# Guide_laser.net
KiCad netlist of a schematic drawn in Altium Designer
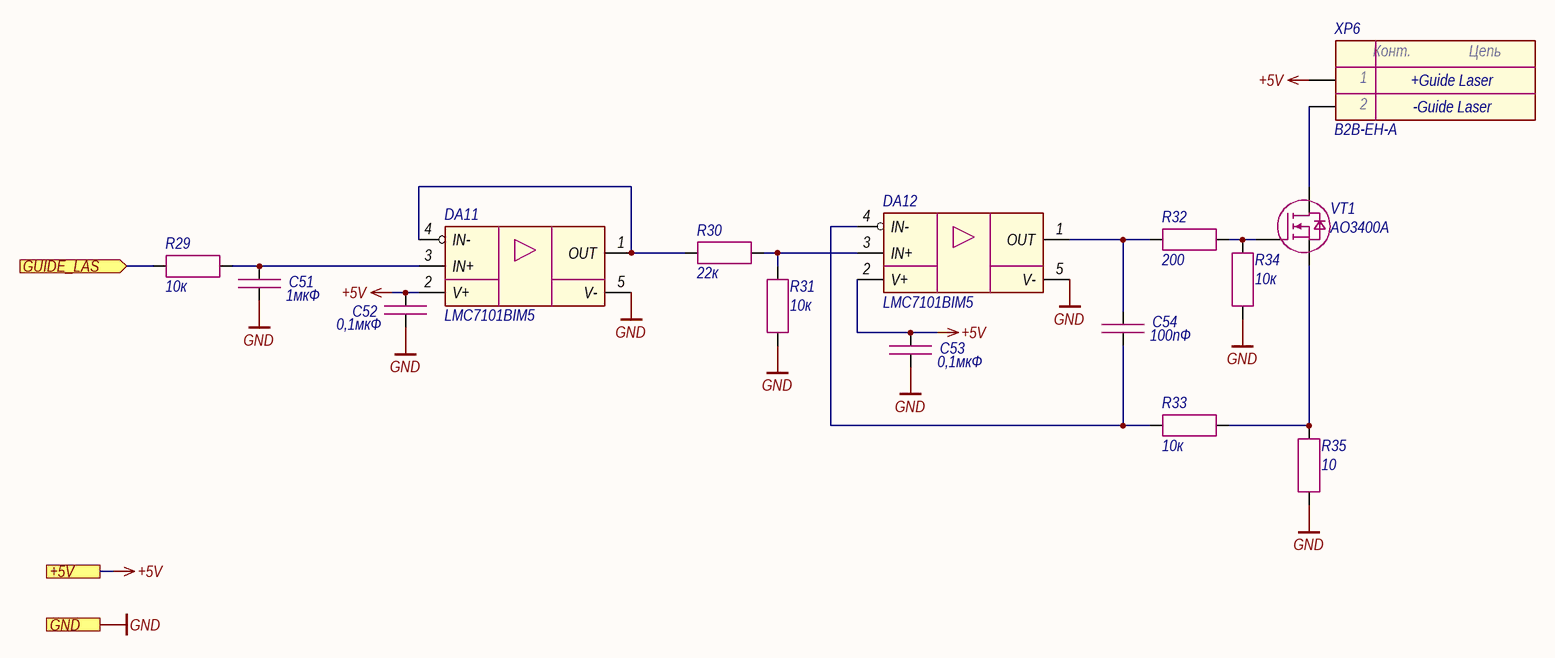
[diagram p0: Guide_laser.SchDoc]

(export (version "E")
  (design (tool "Eeschema 10.0.6"))
  (components
    (comp (ref "C51")
      (value "1мкФ")
      (footprint "Pcb_library:CAP_0603")
      (fields (field (name "MANUFACTURER") "Murata"))
      (libsource (lib "Schem_library") (part "Capacitor"))
    )
    (comp (ref "C52")
      (value "0,1мкФ")
      (footprint "Pcb_library:CAP_0603")
      (fields (field (name "MANUFACTURER") "Murata"))
      (libsource (lib "Schem_library") (part "Capacitor"))
    )
    (comp (ref "C53")
      (value "0,1мкФ")
      (footprint "Pcb_library:CAP_0603")
      (fields (field (name "MANUFACTURER") "Murata"))
      (libsource (lib "Schem_library") (part "Capacitor"))
    )
    (comp (ref "C54")
      (value "100пФ")
      (footprint "Pcb_library:CAP_0603")
      (fields (field (name "MANUFACTURER") "Murata"))
      (libsource (lib "Schem_library") (part "Capacitor"))
    )
    (comp (ref "DA11")
      (value "LMC7101BIM5")
      (footprint "Pcb_library:SOT-23-5")
      (fields (field (name "MANUFACTURER") "Texas Instruments"))
      (libsource (lib "Schem_library") (part "LMC7101"))
    )
    (comp (ref "DA12")
      (value "LMC7101BIM5")
      (footprint "Pcb_library:SOT-23-5")
      (fields (field (name "MANUFACTURER") "Texas Instruments"))
      (libsource (lib "Schem_library") (part "LMC7101"))
    )
    (comp (ref "R29")
      (value "10к")
      (footprint "Pcb_library:RES_0603")
      (fields (field (name "MANUFACTURER") "Yageo"))
      (libsource (lib "Schem_library") (part "Resistor"))
    )
    (comp (ref "R30")
      (value "22к")
      (footprint "Pcb_library:RES_0603")
      (fields (field (name "MANUFACTURER") "Yageo"))
      (libsource (lib "Schem_library") (part "Resistor"))
    )
    (comp (ref "R31")
      (value "10к")
      (footprint "Pcb_library:RES_0603")
      (fields (field (name "MANUFACTURER") "Yageo"))
      (libsource (lib "Schem_library") (part "Resistor"))
    )
    (comp (ref "R32")
      (value "200")
      (footprint "Pcb_library:RES_0603")
      (fields (field (name "MANUFACTURER") "Yageo"))
      (libsource (lib "Schem_library") (part "Resistor"))
    )
    (comp (ref "R33")
      (value "10к")
      (footprint "Pcb_library:RES_0603")
      (fields (field (name "MANUFACTURER") "Yageo"))
      (libsource (lib "Schem_library") (part "Resistor"))
    )
    (comp (ref "R34")
      (value "10к")
      (footprint "Pcb_library:RES_0603")
      (fields (field (name "MANUFACTURER") "Yageo"))
      (libsource (lib "Schem_library") (part "Resistor"))
    )
    (comp (ref "R35")
      (value "10")
      (footprint "Pcb_library:RES_1210")
      (fields (field (name "MANUFACTURER") "Yageo"))
      (libsource (lib "Schem_library") (part "Resistor"))
    )
    (comp (ref "VT1")
      (value "AO3400A")
      (footprint "Pcb_library:SOT-23-3")
      (fields (field (name "MANUFACTURER") "UMW"))
      (libsource (lib "Schem_library") (part "MOSFET N-channel"))
    )
    (comp (ref "XP6")
      (value "B2B-EH-A")
      (footprint "Pcb_library:B2B-EH-A")
      (fields (field (name "MANUFACTURER") "JST"))
      (libsource (lib "Schem_library") (part "Connector-2"))
    )
  )
  (nets
    (net (code "1") (name "+5V") (class "Default")
      (node (ref "C52") (pin "1") (pinfunction "1_1") (pintype "passive"))
      (node (ref "C53") (pin "1") (pinfunction "1_1") (pintype "passive"))
      (node (ref "DA11") (pin "2") (pinfunction "V+_2") (pintype "passive"))
      (node (ref "DA12") (pin "2") (pinfunction "V+_2") (pintype "passive"))
      (node (ref "XP6") (pin "1") (pintype "passive"))
    )
    (net (code "2") (name "/GUIDE_LAS") (class "Default")
      (node (ref "R29") (pin "1") (pinfunction "1_1") (pintype "passive"))
    )
    (net (code "3") (name "GND") (class "Default")
      (node (ref "C51") (pin "2") (pinfunction "2_2") (pintype "passive"))
      (node (ref "C52") (pin "2") (pinfunction "2_2") (pintype "passive"))
      (node (ref "C53") (pin "2") (pinfunction "2_2") (pintype "passive"))
      (node (ref "DA11") (pin "5") (pinfunction "V-_5") (pintype "passive"))
      (node (ref "DA12") (pin "5") (pinfunction "V-_5") (pintype "passive"))
      (node (ref "R31") (pin "2") (pinfunction "2_2") (pintype "passive"))
      (node (ref "R34") (pin "1") (pinfunction "1_1") (pintype "passive"))
      (node (ref "R35") (pin "1") (pinfunction "1_1") (pintype "passive"))
    )
    (net (code "4") (name "Net-(DA11-IN+)") (class "Default")
      (node (ref "C51") (pin "1") (pinfunction "1_1") (pintype "passive"))
      (node (ref "DA11") (pin "3") (pinfunction "IN+_3") (pintype "passive"))
      (node (ref "R29") (pin "2") (pinfunction "2_2") (pintype "passive"))
    )
    (net (code "5") (name "Net-(DA11-IN-)") (class "Default")
      (node (ref "DA11") (pin "1") (pinfunction "OUT_1") (pintype "passive"))
      (node (ref "DA11") (pin "4") (pinfunction "IN-_4") (pintype "passive"))
      (node (ref "R30") (pin "1") (pinfunction "1_1") (pintype "passive"))
    )
    (net (code "6") (name "Net-(DA12-IN+)") (class "Default")
      (node (ref "DA12") (pin "3") (pinfunction "IN+_3") (pintype "passive"))
      (node (ref "R30") (pin "2") (pinfunction "2_2") (pintype "passive"))
      (node (ref "R31") (pin "1") (pinfunction "1_1") (pintype "passive"))
    )
    (net (code "7") (name "Net-(DA12-IN-)") (class "Default")
      (node (ref "C54") (pin "2") (pinfunction "2_2") (pintype "passive"))
      (node (ref "DA12") (pin "4") (pinfunction "IN-_4") (pintype "passive"))
      (node (ref "R33") (pin "1") (pinfunction "1_1") (pintype "passive"))
    )
    (net (code "8") (name "Net-(DA12-OUT)") (class "Default")
      (node (ref "C54") (pin "1") (pinfunction "1_1") (pintype "passive"))
      (node (ref "DA12") (pin "1") (pinfunction "OUT_1") (pintype "passive"))
      (node (ref "R32") (pin "1") (pinfunction "1_1") (pintype "passive"))
    )
    (net (code "9") (name "Net-(VT1-D)") (class "Default")
      (node (ref "VT1") (pin "3") (pinfunction "D_3") (pintype "passive"))
      (node (ref "XP6") (pin "2") (pintype "passive"))
    )
    (net (code "10") (name "Net-(VT1-G)") (class "Default")
      (node (ref "R32") (pin "2") (pinfunction "2_2") (pintype "passive"))
      (node (ref "R34") (pin "2") (pinfunction "2_2") (pintype "passive"))
      (node (ref "VT1") (pin "1") (pinfunction "G_1") (pintype "passive"))
    )
    (net (code "11") (name "Net-(VT1-S)") (class "Default")
      (node (ref "R33") (pin "2") (pinfunction "2_2") (pintype "passive"))
      (node (ref "R35") (pin "2") (pinfunction "2_2") (pintype "passive"))
      (node (ref "VT1") (pin "2") (pinfunction "S_2") (pintype "passive"))
    )
  )
)
